# LT3470.net
KiCad netlist of a schematic drawn in Altium Designer
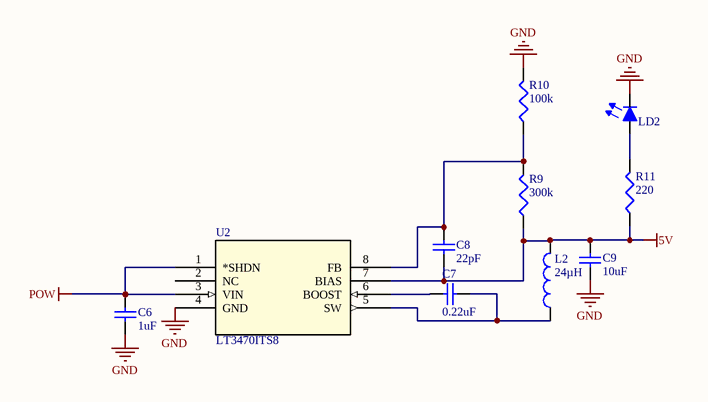
[diagram p0: LT3470.SchDoc]

(export (version "E")
  (design (tool "Eeschema 10.0.6"))
  (components
    (comp (ref "C6")
      (value "1uF")
      (footprint "0805 CAP")
      (fields
        (field (name "MANUFACTURER") "Murata")
        (field (name "MANUFACTURER PART NUMBER") "GCM21BR7YA105KA55L")
      )
      (libsource (lib "charger_LT3652") (part "1uF/0805"))
    )
    (comp (ref "C7")
      (value "0.22uF")
      (footprint "0805 CAP")
      (fields
        (field (name "MANUFACTURER") "Murata")
        (field (name "MANUFACTURER PART NUMBER") "GCM21BR7YA105KA55L")
      )
      (libsource (lib "charger_LT3652") (part "1uF/0805"))
    )
    (comp (ref "C8")
      (value "22pF")
      (footprint "0805 CAP")
      (fields
        (field (name "MANUFACTURER") "Murata")
        (field (name "MANUFACTURER PART NUMBER") "GCM21BR7YA105KA55L")
      )
      (libsource (lib "charger_LT3652") (part "1uF/0805"))
    )
    (comp (ref "C9")
      (value "10uF")
      (footprint "0805 CAP")
      (fields
        (field (name "MANUFACTURER") "Murata")
        (field (name "MANUFACTURER PART NUMBER") "GCM21BR7YA105KA55L")
      )
      (libsource (lib "charger_LT3652") (part "1uF/0805"))
    )
    (comp (ref "L2")
      (value "24µH")
      (footprint "INDPM7070X580N")
      (description "Inductance")
      (fields (field (name "DESIGNER") "ECAM 2003"))
      (libsource (lib "charger_LT3652") (part "Inductance"))
    )
    (comp (ref "LD2")
      (value "green")
      (footprint "LED_0603")
      (description "LED green")
      (fields (field (name "MANUFACTURER") "Multicomp") (field (name "MANUFACTURER PART NUMBER") "703-0112"))
      (libsource (lib "charger_LT3652") (part "LED diode"))
    )
    (comp (ref "R9")
      (value "300k")
      (footprint "0603 RES")
      (description "Résistance standard")
      (fields (field (name "Comment") "Résistance") (field (name "DESIGNER") "ECAM 2005"))
      (libsource (lib "charger_LT3652") (part "Résistance"))
    )
    (comp (ref "R10")
      (value "100k")
      (footprint "0603 RES")
      (description "Résistance standard")
      (fields (field (name "Comment") "Résistance") (field (name "DESIGNER") "ECAM 2005"))
      (libsource (lib "charger_LT3652") (part "Résistance"))
    )
    (comp (ref "R11")
      (value "220")
      (footprint "0603 RES")
      (description "Résistance standard")
      (fields (field (name "Comment") "Résistance") (field (name "DESIGNER") "ECAM 2005"))
      (libsource (lib "charger_LT3652") (part "Résistance"))
    )
    (comp (ref "U2")
      (value "LT3470ITS8")
      (footprint "TSOT-23_TS8")
      (description "No Description Available")
      (fields (field (name "COPYRIGHT") "Copyright (C) 2018 Accelerated Designs. All rights reserved"))
      (libsource (lib "charger_LT3652") (part "LT3470ITS8"))
    )
  )
  (nets
    (net (code "1") (name "5V") (class "Default")
      (node (ref "C8") (pin "1") (pinfunction "1_1") (pintype "passive"))
      (node (ref "C9") (pin "1") (pinfunction "1_1") (pintype "passive"))
      (node (ref "L2") (pin "2") (pinfunction "2_2") (pintype "passive"))
      (node (ref "R11") (pin "1") (pinfunction "1_1") (pintype "passive"))
      (node (ref "R9") (pin "1") (pinfunction "1_1") (pintype "passive"))
      (node (ref "U2") (pin "7") (pinfunction "BIAS_7") (pintype "passive"))
    )
    (net (code "2") (name "GND") (class "Default")
      (node (ref "C6") (pin "1") (pinfunction "1_1") (pintype "passive"))
      (node (ref "C9") (pin "2") (pinfunction "2_2") (pintype "passive"))
      (node (ref "LD2") (pin "2") (pinfunction "K_2") (pintype "passive"))
      (node (ref "R10") (pin "2") (pinfunction "2_2") (pintype "passive"))
      (node (ref "U2") (pin "4") (pinfunction "GND_4") (pintype "power_in"))
    )
    (net (code "3") (name "Net-(LD2-A1)") (class "Default")
      (node (ref "LD2") (pin "1") (pinfunction "A1_1") (pintype "passive"))
      (node (ref "R11") (pin "2") (pinfunction "2_2") (pintype "passive"))
    )
    (net (code "4") (name "Net-(U2-BOOST)") (class "Default")
      (node (ref "C7") (pin "1") (pinfunction "1_1") (pintype "passive"))
      (node (ref "U2") (pin "6") (pinfunction "BOOST_6") (pintype "input"))
    )
    (net (code "5") (name "Net-(U2-FB)") (class "Default")
      (node (ref "C8") (pin "2") (pinfunction "2_2") (pintype "passive"))
      (node (ref "R10") (pin "1") (pinfunction "1_1") (pintype "passive"))
      (node (ref "R9") (pin "2") (pinfunction "2_2") (pintype "passive"))
      (node (ref "U2") (pin "8") (pinfunction "FB_8") (pintype "passive"))
    )
    (net (code "6") (name "Net-(U2-SW)") (class "Default")
      (node (ref "C7") (pin "2") (pinfunction "2_2") (pintype "passive"))
      (node (ref "L2") (pin "1") (pinfunction "1_1") (pintype "passive"))
      (node (ref "U2") (pin "5") (pinfunction "SW_5") (pintype "output"))
    )
    (net (code "7") (name "POW") (class "Default")
      (node (ref "C6") (pin "2") (pinfunction "2_2") (pintype "passive"))
      (node (ref "U2") (pin "1") (pinfunction "*SHDN_1") (pintype "passive"))
      (node (ref "U2") (pin "3") (pinfunction "VIN_3") (pintype "input"))
    )
    (net (code "8") (name "unconnected-(U2-NC-Pad2)") (class "Default")
      (node (ref "U2") (pin "2") (pinfunction "NC_2") (pintype "passive"))
    )
  )
)
